# IMx6Q.net
KiCad netlist of a schematic drawn in Altium Designer
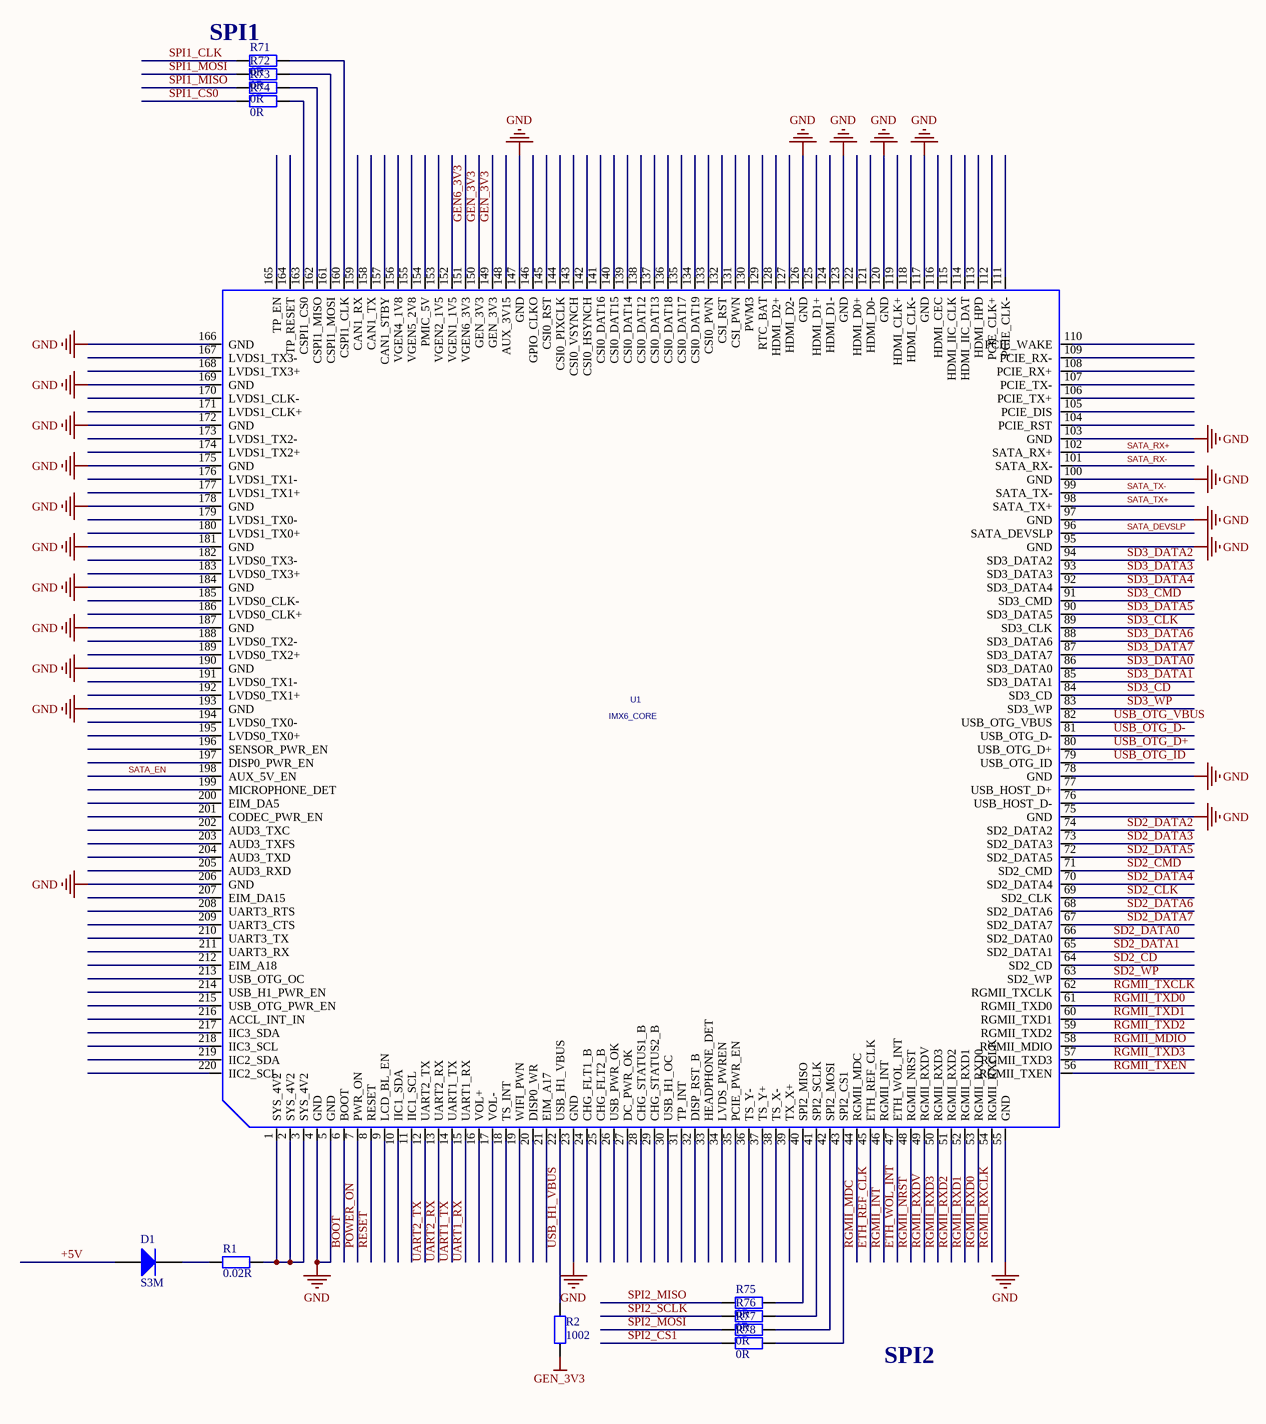
[diagram p0: IMx6Q.SchDoc]

(export (version "E")
  (design (tool "Eeschema 10.0.6"))
  (components
    (comp (ref "D1")
      (value "S3M")
      (footprint "DSO-C2/X3.3")
      (description "Default Diode")
      (fields (field (name "PUBLISHER") "Altium Limited"))
      (libsource (lib "Miscellaneous Devices") (part "Diode"))
    )
    (comp (ref "R1")
      (value "0.02R")
      (footprint "R1210")
      (description "Resistor")
      (fields (field (name "PUBLISHER") "Altium Limited"))
      (libsource (lib "") (part "Res2_1"))
    )
    (comp (ref "R2")
      (value "1002")
      (footprint "0603")
      (description "Resistor")
      (fields (field (name "PUBLISHER") "Altium Limited"))
      (libsource (lib "Miscellaneous Devices") (part "Res2"))
    )
    (comp (ref "R71") (value "0R") (footprint "0603") (libsource (lib "贴片电容电阻等") (part "电阻")))
    (comp (ref "R72") (value "0R") (footprint "0603") (libsource (lib "贴片电容电阻等") (part "电阻")))
    (comp (ref "R73") (value "0R") (footprint "0603") (libsource (lib "贴片电容电阻等") (part "电阻")))
    (comp (ref "R74") (value "0R") (footprint "0603") (libsource (lib "贴片电容电阻等") (part "电阻")))
    (comp (ref "R75") (value "0R") (footprint "0603") (libsource (lib "贴片电容电阻等") (part "电阻")))
    (comp (ref "R76") (value "0R") (footprint "0603") (libsource (lib "贴片电容电阻等") (part "电阻")))
    (comp (ref "R77") (value "0R") (footprint "0603") (libsource (lib "贴片电容电阻等") (part "电阻")))
    (comp (ref "R78") (value "0R") (footprint "0603") (libsource (lib "贴片电容电阻等") (part "电阻")))
    (comp (ref "U1") (value "IMX6_CORE") (footprint "IMX6_CORE") (libsource (lib "*") (part "IMX6_CORE")))
  )
  (nets
    (net (code "1") (name "/+5V") (class "Default")
      (node (ref "D1") (pin "1") (pinfunction "A_1") (pintype "passive"))
    )
    (net (code "2") (name "/BOOT") (class "Default")
      (node (ref "U1") (pin "6") (pinfunction "BOOT_6") (pintype "passive"))
    )
    (net (code "3") (name "/ETH_REF_CLK") (class "Default")
      (node (ref "U1") (pin "45") (pinfunction "ETH_REF_CLK_45") (pintype "passive"))
    )
    (net (code "4") (name "/ETH_WOL_INT") (class "Default")
      (node (ref "U1") (pin "47") (pinfunction "ETH_WOL_INT_47") (pintype "passive"))
    )
    (net (code "5") (name "/GEN6_3V3") (class "Default")
      (node (ref "U1") (pin "151") (pinfunction "VGEN6_3V3_151") (pintype "passive"))
    )
    (net (code "6") (name "/POWER_ON") (class "Default")
      (node (ref "U1") (pin "7") (pinfunction "PWR_ON_7") (pintype "passive"))
    )
    (net (code "7") (name "/RESET") (class "Default")
      (node (ref "U1") (pin "8") (pinfunction "RESET_8") (pintype "passive"))
    )
    (net (code "8") (name "/RGMII_INT") (class "Default")
      (node (ref "U1") (pin "46") (pinfunction "RGMII_INT_46") (pintype "passive"))
    )
    (net (code "9") (name "/RGMII_MDC") (class "Default")
      (node (ref "U1") (pin "44") (pinfunction "RGMII_MDC_44") (pintype "passive"))
    )
    (net (code "10") (name "/RGMII_MDIO") (class "Default")
      (node (ref "U1") (pin "58") (pinfunction "RGMII_MDIO_58") (pintype "passive"))
    )
    (net (code "11") (name "/RGMII_NRST") (class "Default")
      (node (ref "U1") (pin "48") (pinfunction "RGMII_NRST_48") (pintype "passive"))
    )
    (net (code "12") (name "/RGMII_RXCLK") (class "Default")
      (node (ref "U1") (pin "54") (pinfunction "RGMII_RXCLK_54") (pintype "passive"))
    )
    (net (code "13") (name "/RGMII_RXD0") (class "Default")
      (node (ref "U1") (pin "53") (pinfunction "RGMII_RXD0_53") (pintype "passive"))
    )
    (net (code "14") (name "/RGMII_RXD1") (class "Default")
      (node (ref "U1") (pin "52") (pinfunction "RGMII_RXD1_52") (pintype "passive"))
    )
    (net (code "15") (name "/RGMII_RXD2") (class "Default")
      (node (ref "U1") (pin "51") (pinfunction "RGMII_RXD2_51") (pintype "passive"))
    )
    (net (code "16") (name "/RGMII_RXD3") (class "Default")
      (node (ref "U1") (pin "50") (pinfunction "RGMII_RXD3_50") (pintype "passive"))
    )
    (net (code "17") (name "/RGMII_RXDV") (class "Default")
      (node (ref "U1") (pin "49") (pinfunction "RGMII_RXDV_49") (pintype "passive"))
    )
    (net (code "18") (name "/RGMII_TXCLK") (class "Default")
      (node (ref "U1") (pin "62") (pinfunction "RGMII_TXCLK_62") (pintype "passive"))
    )
    (net (code "19") (name "/RGMII_TXD0") (class "Default")
      (node (ref "U1") (pin "61") (pinfunction "RGMII_TXD0_61") (pintype "passive"))
    )
    (net (code "20") (name "/RGMII_TXD1") (class "Default")
      (node (ref "U1") (pin "60") (pinfunction "RGMII_TXD1_60") (pintype "passive"))
    )
    (net (code "21") (name "/RGMII_TXD2") (class "Default")
      (node (ref "U1") (pin "59") (pinfunction "RGMII_TXD2_59") (pintype "passive"))
    )
    (net (code "22") (name "/RGMII_TXD3") (class "Default")
      (node (ref "U1") (pin "57") (pinfunction "RGMII_TXD3_57") (pintype "passive"))
    )
    (net (code "23") (name "/RGMII_TXEN") (class "Default")
      (node (ref "U1") (pin "56") (pinfunction "RGMII_TXEN_56") (pintype "passive"))
    )
    (net (code "24") (name "/SATA_DEVSLP") (class "Default")
      (node (ref "U1") (pin "96") (pinfunction "SATA_DEVSLP_96") (pintype "passive"))
    )
    (net (code "25") (name "/SATA_EN") (class "Default")
      (node (ref "U1") (pin "198") (pinfunction "AUX_5V_EN_198") (pintype "passive"))
    )
    (net (code "26") (name "/SATA_RX+") (class "Default")
      (node (ref "U1") (pin "102") (pinfunction "SATA_RX+_102") (pintype "passive"))
    )
    (net (code "27") (name "/SATA_RX-") (class "Default")
      (node (ref "U1") (pin "101") (pinfunction "SATA_RX-_101") (pintype "passive"))
    )
    (net (code "28") (name "/SATA_TX+") (class "Default")
      (node (ref "U1") (pin "98") (pinfunction "SATA_TX+_98") (pintype "passive"))
    )
    (net (code "29") (name "/SATA_TX-") (class "Default")
      (node (ref "U1") (pin "99") (pinfunction "SATA_TX-_99") (pintype "passive"))
    )
    (net (code "30") (name "/SD2_CD") (class "Default")
      (node (ref "U1") (pin "64") (pinfunction "SD2_CD_64") (pintype "passive"))
    )
    (net (code "31") (name "/SD2_CLK") (class "Default")
      (node (ref "U1") (pin "69") (pinfunction "SD2_CLK_69") (pintype "passive"))
    )
    (net (code "32") (name "/SD2_CMD") (class "Default")
      (node (ref "U1") (pin "71") (pinfunction "SD2_CMD_71") (pintype "passive"))
    )
    (net (code "33") (name "/SD2_DATA0") (class "Default")
      (node (ref "U1") (pin "66") (pinfunction "SD2_DATA0_66") (pintype "passive"))
    )
    (net (code "34") (name "/SD2_DATA1") (class "Default")
      (node (ref "U1") (pin "65") (pinfunction "SD2_DATA1_65") (pintype "passive"))
    )
    (net (code "35") (name "/SD2_DATA2") (class "Default")
      (node (ref "U1") (pin "74") (pinfunction "SD2_DATA2_74") (pintype "passive"))
    )
    (net (code "36") (name "/SD2_DATA3") (class "Default")
      (node (ref "U1") (pin "73") (pinfunction "SD2_DATA3_73") (pintype "passive"))
    )
    (net (code "37") (name "/SD2_DATA4") (class "Default")
      (node (ref "U1") (pin "70") (pinfunction "SD2_DATA4_70") (pintype "passive"))
    )
    (net (code "38") (name "/SD2_DATA5") (class "Default")
      (node (ref "U1") (pin "72") (pinfunction "SD2_DATA5_72") (pintype "passive"))
    )
    (net (code "39") (name "/SD2_DATA6") (class "Default")
      (node (ref "U1") (pin "68") (pinfunction "SD2_DATA6_68") (pintype "passive"))
    )
    (net (code "40") (name "/SD2_DATA7") (class "Default")
      (node (ref "U1") (pin "67") (pinfunction "SD2_DATA7_67") (pintype "passive"))
    )
    (net (code "41") (name "/SD2_WP") (class "Default")
      (node (ref "U1") (pin "63") (pinfunction "SD2_WP_63") (pintype "passive"))
    )
    (net (code "42") (name "/SD3_CD") (class "Default")
      (node (ref "U1") (pin "84") (pinfunction "SD3_CD_84") (pintype "passive"))
    )
    (net (code "43") (name "/SD3_CLK") (class "Default")
      (node (ref "U1") (pin "89") (pinfunction "SD3_CLK_89") (pintype "passive"))
    )
    (net (code "44") (name "/SD3_CMD") (class "Default")
      (node (ref "U1") (pin "91") (pinfunction "SD3_CMD_91") (pintype "passive"))
    )
    (net (code "45") (name "/SD3_DATA0") (class "Default")
      (node (ref "U1") (pin "86") (pinfunction "SD3_DATA0_86") (pintype "passive"))
    )
    (net (code "46") (name "/SD3_DATA1") (class "Default")
      (node (ref "U1") (pin "85") (pinfunction "SD3_DATA1_85") (pintype "passive"))
    )
    (net (code "47") (name "/SD3_DATA2") (class "Default")
      (node (ref "U1") (pin "94") (pinfunction "SD3_DATA2_94") (pintype "passive"))
    )
    (net (code "48") (name "/SD3_DATA3") (class "Default")
      (node (ref "U1") (pin "93") (pinfunction "SD3_DATA3_93") (pintype "passive"))
    )
    (net (code "49") (name "/SD3_DATA4") (class "Default")
      (node (ref "U1") (pin "92") (pinfunction "SD3_DATA4_92") (pintype "passive"))
    )
    (net (code "50") (name "/SD3_DATA5") (class "Default")
      (node (ref "U1") (pin "90") (pinfunction "SD3_DATA5_90") (pintype "passive"))
    )
    (net (code "51") (name "/SD3_DATA6") (class "Default")
      (node (ref "U1") (pin "88") (pinfunction "SD3_DATA6_88") (pintype "passive"))
    )
    (net (code "52") (name "/SD3_DATA7") (class "Default")
      (node (ref "U1") (pin "87") (pinfunction "SD3_DATA7_87") (pintype "passive"))
    )
    (net (code "53") (name "/SD3_WP") (class "Default")
      (node (ref "U1") (pin "83") (pinfunction "SD3_WP_83") (pintype "passive"))
    )
    (net (code "54") (name "/SPI1_CLK") (class "Default")
      (node (ref "R71") (pin "2") (pinfunction "2_2") (pintype "passive"))
    )
    (net (code "55") (name "/SPI1_CS0") (class "Default")
      (node (ref "R74") (pin "2") (pinfunction "2_2") (pintype "passive"))
    )
    (net (code "56") (name "/SPI1_MISO") (class "Default")
      (node (ref "R73") (pin "2") (pinfunction "2_2") (pintype "passive"))
    )
    (net (code "57") (name "/SPI1_MOSI") (class "Default")
      (node (ref "R72") (pin "2") (pinfunction "2_2") (pintype "passive"))
    )
    (net (code "58") (name "/SPI2_CS1") (class "Default")
      (node (ref "R78") (pin "2") (pinfunction "2_2") (pintype "passive"))
    )
    (net (code "59") (name "/SPI2_MISO") (class "Default")
      (node (ref "R75") (pin "2") (pinfunction "2_2") (pintype "passive"))
    )
    (net (code "60") (name "/SPI2_MOSI") (class "Default")
      (node (ref "R77") (pin "2") (pinfunction "2_2") (pintype "passive"))
    )
    (net (code "61") (name "/SPI2_SCLK") (class "Default")
      (node (ref "R76") (pin "2") (pinfunction "2_2") (pintype "passive"))
    )
    (net (code "62") (name "/UART1_RX") (class "Default")
      (node (ref "U1") (pin "15") (pinfunction "UART1_RX_15") (pintype "passive"))
    )
    (net (code "63") (name "/UART1_TX") (class "Default")
      (node (ref "U1") (pin "14") (pinfunction "UART1_TX_14") (pintype "passive"))
    )
    (net (code "64") (name "/UART2_RX") (class "Default")
      (node (ref "U1") (pin "13") (pinfunction "UART2_RX_13") (pintype "passive"))
    )
    (net (code "65") (name "/UART2_TX") (class "Default")
      (node (ref "U1") (pin "12") (pinfunction "UART2_TX_12") (pintype "passive"))
    )
    (net (code "66") (name "/USB_H1_VBUS") (class "Default")
      (node (ref "R2") (pin "1") (pinfunction "1_1") (pintype "passive"))
      (node (ref "U1") (pin "22") (pinfunction "USB_H1_VBUS_22") (pintype "passive"))
    )
    (net (code "67") (name "/USB_OTG_D+") (class "Default")
      (node (ref "U1") (pin "80") (pinfunction "USB_OTG_D+_80") (pintype "passive"))
    )
    (net (code "68") (name "/USB_OTG_D-") (class "Default")
      (node (ref "U1") (pin "81") (pinfunction "USB_OTG_D-_81") (pintype "passive"))
    )
    (net (code "69") (name "/USB_OTG_ID") (class "Default")
      (node (ref "U1") (pin "79") (pinfunction "USB_OTG_ID_79") (pintype "passive"))
    )
    (net (code "70") (name "/USB_OTG_VBUS") (class "Default")
      (node (ref "U1") (pin "82") (pinfunction "USB_OTG_VBUS_82") (pintype "passive"))
    )
    (net (code "71") (name "GEN_3V3") (class "Default")
      (node (ref "R2") (pin "2") (pinfunction "2_2") (pintype "passive"))
      (node (ref "U1") (pin "149") (pinfunction "GEN_3V3_149") (pintype "passive"))
      (node (ref "U1") (pin "150") (pinfunction "GEN_3V3_150") (pintype "passive"))
    )
    (net (code "72") (name "GND") (class "Default")
      (node (ref "U1") (pin "100") (pinfunction "GND_100") (pintype "passive"))
      (node (ref "U1") (pin "103") (pinfunction "GND_103") (pintype "passive"))
      (node (ref "U1") (pin "117") (pinfunction "GND_117") (pintype "passive"))
      (node (ref "U1") (pin "120") (pinfunction "GND_120") (pintype "passive"))
      (node (ref "U1") (pin "123") (pinfunction "GND_123") (pintype "passive"))
      (node (ref "U1") (pin "126") (pinfunction "GND_126") (pintype "passive"))
      (node (ref "U1") (pin "147") (pinfunction "GND_147") (pintype "passive"))
      (node (ref "U1") (pin "166") (pinfunction "GND_166") (pintype "passive"))
      (node (ref "U1") (pin "169") (pinfunction "GND_169") (pintype "passive"))
      (node (ref "U1") (pin "172") (pinfunction "GND_172") (pintype "passive"))
      (node (ref "U1") (pin "175") (pinfunction "GND_175") (pintype "passive"))
      (node (ref "U1") (pin "178") (pinfunction "GND_178") (pintype "passive"))
      (node (ref "U1") (pin "181") (pinfunction "GND_181") (pintype "passive"))
      (node (ref "U1") (pin "184") (pinfunction "GND_184") (pintype "passive"))
      (node (ref "U1") (pin "187") (pinfunction "GND_187") (pintype "passive"))
      (node (ref "U1") (pin "190") (pinfunction "GND_190") (pintype "passive"))
      (node (ref "U1") (pin "193") (pinfunction "GND_193") (pintype "passive"))
      (node (ref "U1") (pin "206") (pinfunction "GND_206") (pintype "passive"))
      (node (ref "U1") (pin "23") (pinfunction "GND_23") (pintype "passive"))
      (node (ref "U1") (pin "4") (pinfunction "GND_4") (pintype "passive"))
      (node (ref "U1") (pin "5") (pinfunction "GND_5") (pintype "passive"))
      (node (ref "U1") (pin "55") (pinfunction "GND_55") (pintype "passive"))
      (node (ref "U1") (pin "75") (pinfunction "GND_75") (pintype "passive"))
      (node (ref "U1") (pin "78") (pinfunction "GND_78") (pintype "passive"))
      (node (ref "U1") (pin "95") (pinfunction "GND_95") (pintype "passive"))
      (node (ref "U1") (pin "97") (pinfunction "GND_97") (pintype "passive"))
    )
    (net (code "73") (name "Net-(D1-K)") (class "Default")
      (node (ref "D1") (pin "2") (pinfunction "K_2") (pintype "passive"))
      (node (ref "R1") (pin "1") (pinfunction "1_1") (pintype "passive"))
    )
    (net (code "74") (name "Net-(R1-Pad2)") (class "Default")
      (node (ref "R1") (pin "2") (pinfunction "2_2") (pintype "passive"))
      (node (ref "U1") (pin "1") (pinfunction "SYS_4V2_1") (pintype "passive"))
      (node (ref "U1") (pin "2") (pinfunction "SYS_4V2_2") (pintype "passive"))
      (node (ref "U1") (pin "3") (pinfunction "SYS_4V2_3") (pintype "passive"))
    )
    (net (code "75") (name "Net-(U1-CSPI1_CLK)") (class "Default")
      (node (ref "R71") (pin "1") (pinfunction "1_1") (pintype "passive"))
      (node (ref "U1") (pin "160") (pinfunction "CSPI1_CLK_160") (pintype "passive"))
    )
    (net (code "76") (name "Net-(U1-CSPI1_CS0)") (class "Default")
      (node (ref "R74") (pin "1") (pinfunction "1_1") (pintype "passive"))
      (node (ref "U1") (pin "163") (pinfunction "CSPI1_CS0_163") (pintype "passive"))
    )
    (net (code "77") (name "Net-(U1-CSPI1_MISO)") (class "Default")
      (node (ref "R73") (pin "1") (pinfunction "1_1") (pintype "passive"))
      (node (ref "U1") (pin "162") (pinfunction "CSPI1_MISO_162") (pintype "passive"))
    )
    (net (code "78") (name "Net-(U1-CSPI1_MOSI)") (class "Default")
      (node (ref "R72") (pin "1") (pinfunction "1_1") (pintype "passive"))
      (node (ref "U1") (pin "161") (pinfunction "CSPI1_MOSI_161") (pintype "passive"))
    )
    (net (code "79") (name "Net-(U1-SPI2_CS1)") (class "Default")
      (node (ref "R78") (pin "1") (pinfunction "1_1") (pintype "passive"))
      (node (ref "U1") (pin "43") (pinfunction "SPI2_CS1_43") (pintype "passive"))
    )
    (net (code "80") (name "Net-(U1-SPI2_MISO)") (class "Default")
      (node (ref "R75") (pin "1") (pinfunction "1_1") (pintype "passive"))
      (node (ref "U1") (pin "40") (pinfunction "SPI2_MISO_40") (pintype "passive"))
    )
    (net (code "81") (name "Net-(U1-SPI2_MOSI)") (class "Default")
      (node (ref "R77") (pin "1") (pinfunction "1_1") (pintype "passive"))
      (node (ref "U1") (pin "42") (pinfunction "SPI2_MOSI_42") (pintype "passive"))
    )
    (net (code "82") (name "Net-(U1-SPI2_SCLK)") (class "Default")
      (node (ref "R76") (pin "1") (pinfunction "1_1") (pintype "passive"))
      (node (ref "U1") (pin "41") (pinfunction "SPI2_SCLK_41") (pintype "passive"))
    )
    (net (code "83") (name "unconnected-(U1-ACCL_INT_IN-Pad216)") (class "Default")
      (node (ref "U1") (pin "216") (pinfunction "ACCL_INT_IN_216") (pintype "passive"))
    )
    (net (code "84") (name "unconnected-(U1-AUD3_RXD-Pad205)") (class "Default")
      (node (ref "U1") (pin "205") (pinfunction "AUD3_RXD_205") (pintype "passive"))
    )
    (net (code "85") (name "unconnected-(U1-AUD3_TXC-Pad202)") (class "Default")
      (node (ref "U1") (pin "202") (pinfunction "AUD3_TXC_202") (pintype "passive"))
    )
    (net (code "86") (name "unconnected-(U1-AUD3_TXD-Pad204)") (class "Default")
      (node (ref "U1") (pin "204") (pinfunction "AUD3_TXD_204") (pintype "passive"))
    )
    (net (code "87") (name "unconnected-(U1-AUD3_TXFS-Pad203)") (class "Default")
      (node (ref "U1") (pin "203") (pinfunction "AUD3_TXFS_203") (pintype "passive"))
    )
    (net (code "88") (name "unconnected-(U1-AUX_3V15-Pad148)") (class "Default")
      (node (ref "U1") (pin "148") (pinfunction "AUX_3V15_148") (pintype "passive"))
    )
    (net (code "89") (name "unconnected-(U1-CAN1_RX-Pad159)") (class "Default")
      (node (ref "U1") (pin "159") (pinfunction "CAN1_RX_159") (pintype "passive"))
    )
    (net (code "90") (name "unconnected-(U1-CAN1_STBY-Pad157)") (class "Default")
      (node (ref "U1") (pin "157") (pinfunction "CAN1_STBY_157") (pintype "passive"))
    )
    (net (code "91") (name "unconnected-(U1-CAN1_TX-Pad158)") (class "Default")
      (node (ref "U1") (pin "158") (pinfunction "CAN1_TX_158") (pintype "passive"))
    )
    (net (code "92") (name "unconnected-(U1-CHG_FLT1_B-Pad24)") (class "Default")
      (node (ref "U1") (pin "24") (pinfunction "CHG_FLT1_B_24") (pintype "passive"))
    )
    (net (code "93") (name "unconnected-(U1-CHG_FLT2_B-Pad25)") (class "Default")
      (node (ref "U1") (pin "25") (pinfunction "CHG_FLT2_B_25") (pintype "passive"))
    )
    (net (code "94") (name "unconnected-(U1-CHG_STATUS1_B-Pad28)") (class "Default")
      (node (ref "U1") (pin "28") (pinfunction "CHG_STATUS1_B_28") (pintype "passive"))
    )
    (net (code "95") (name "unconnected-(U1-CHG_STATUS2_B-Pad29)") (class "Default")
      (node (ref "U1") (pin "29") (pinfunction "CHG_STATUS2_B_29") (pintype "passive"))
    )
    (net (code "96") (name "unconnected-(U1-CODEC_PWR_EN-Pad201)") (class "Default")
      (node (ref "U1") (pin "201") (pinfunction "CODEC_PWR_EN_201") (pintype "passive"))
    )
    (net (code "97") (name "unconnected-(U1-CSI0_DAT12-Pad138)") (class "Default")
      (node (ref "U1") (pin "138") (pinfunction "CSI0_DAT12_138") (pintype "passive"))
    )
    (net (code "98") (name "unconnected-(U1-CSI0_DAT13-Pad137)") (class "Default")
      (node (ref "U1") (pin "137") (pinfunction "CSI0_DAT13_137") (pintype "passive"))
    )
    (net (code "99") (name "unconnected-(U1-CSI0_DAT14-Pad139)") (class "Default")
      (node (ref "U1") (pin "139") (pinfunction "CSI0_DAT14_139") (pintype "passive"))
    )
    (net (code "100") (name "unconnected-(U1-CSI0_DAT15-Pad140)") (class "Default")
      (node (ref "U1") (pin "140") (pinfunction "CSI0_DAT15_140") (pintype "passive"))
    )
    (net (code "101") (name "unconnected-(U1-CSI0_DAT16-Pad141)") (class "Default")
      (node (ref "U1") (pin "141") (pinfunction "CSI0_DAT16_141") (pintype "passive"))
    )
    (net (code "102") (name "unconnected-(U1-CSI0_DAT17-Pad135)") (class "Default")
      (node (ref "U1") (pin "135") (pinfunction "CSI0_DAT17_135") (pintype "passive"))
    )
    (net (code "103") (name "unconnected-(U1-CSI0_DAT18-Pad136)") (class "Default")
      (node (ref "U1") (pin "136") (pinfunction "CSI0_DAT18_136") (pintype "passive"))
    )
    (net (code "104") (name "unconnected-(U1-CSI0_DAT19-Pad134)") (class "Default")
      (node (ref "U1") (pin "134") (pinfunction "CSI0_DAT19_134") (pintype "passive"))
    )
    (net (code "105") (name "unconnected-(U1-CSI0_HSYNCH-Pad142)") (class "Default")
      (node (ref "U1") (pin "142") (pinfunction "CSI0_HSYNCH_142") (pintype "passive"))
    )
    (net (code "106") (name "unconnected-(U1-CSI0_PIXCLK-Pad144)") (class "Default")
      (node (ref "U1") (pin "144") (pinfunction "CSI0_PIXCLK_144") (pintype "passive"))
    )
    (net (code "107") (name "unconnected-(U1-CSI0_PWN-Pad133)") (class "Default")
      (node (ref "U1") (pin "133") (pinfunction "CSI0_PWN_133") (pintype "passive"))
    )
    (net (code "108") (name "unconnected-(U1-CSI0_RST-Pad145)") (class "Default")
      (node (ref "U1") (pin "145") (pinfunction "CSI0_RST_145") (pintype "passive"))
    )
    (net (code "109") (name "unconnected-(U1-CSI0_VSYNCH-Pad143)") (class "Default")
      (node (ref "U1") (pin "143") (pinfunction "CSI0_VSYNCH_143") (pintype "passive"))
    )
    (net (code "110") (name "unconnected-(U1-CSI_PWN-Pad131)") (class "Default")
      (node (ref "U1") (pin "131") (pinfunction "CSI_PWN_131") (pintype "passive"))
    )
    (net (code "111") (name "unconnected-(U1-CSI_RST-Pad132)") (class "Default")
      (node (ref "U1") (pin "132") (pinfunction "CSI_RST_132") (pintype "passive"))
    )
    (net (code "112") (name "unconnected-(U1-DC_PWR_OK-Pad27)") (class "Default")
      (node (ref "U1") (pin "27") (pinfunction "DC_PWR_OK_27") (pintype "passive"))
    )
    (net (code "113") (name "unconnected-(U1-DISP0_PWR_EN-Pad197)") (class "Default")
      (node (ref "U1") (pin "197") (pinfunction "DISP0_PWR_EN_197") (pintype "passive"))
    )
    (net (code "114") (name "unconnected-(U1-DISP0_WR-Pad20)") (class "Default")
      (node (ref "U1") (pin "20") (pinfunction "DISP0_WR_20") (pintype "passive"))
    )
    (net (code "115") (name "unconnected-(U1-DISP_RST_B-Pad32)") (class "Default")
      (node (ref "U1") (pin "32") (pinfunction "DISP_RST_B_32") (pintype "passive"))
    )
    (net (code "116") (name "unconnected-(U1-EIM_A17-Pad21)") (class "Default")
      (node (ref "U1") (pin "21") (pinfunction "EIM_A17_21") (pintype "passive"))
    )
    (net (code "117") (name "unconnected-(U1-EIM_A18-Pad212)") (class "Default")
      (node (ref "U1") (pin "212") (pinfunction "EIM_A18_212") (pintype "passive"))
    )
    (net (code "118") (name "unconnected-(U1-EIM_DA5-Pad200)") (class "Default")
      (node (ref "U1") (pin "200") (pinfunction "EIM_DA5_200") (pintype "passive"))
    )
    (net (code "119") (name "unconnected-(U1-EIM_DA15-Pad207)") (class "Default")
      (node (ref "U1") (pin "207") (pinfunction "EIM_DA15_207") (pintype "passive"))
    )
    (net (code "120") (name "unconnected-(U1-GPIO_CLKO-Pad146)") (class "Default")
      (node (ref "U1") (pin "146") (pinfunction "GPIO_CLKO_146") (pintype "passive"))
    )
    (net (code "121") (name "unconnected-(U1-HDMI_CEC-Pad116)") (class "Default")
      (node (ref "U1") (pin "116") (pinfunction "HDMI_CEC_116") (pintype "passive"))
    )
    (net (code "122") (name "unconnected-(U1-HDMI_CLK+-Pad119)") (class "Default")
      (node (ref "U1") (pin "119") (pinfunction "HDMI_CLK+_119") (pintype "passive"))
    )
    (net (code "123") (name "unconnected-(U1-HDMI_CLK--Pad118)") (class "Default")
      (node (ref "U1") (pin "118") (pinfunction "HDMI_CLK-_118") (pintype "passive"))
    )
    (net (code "124") (name "unconnected-(U1-HDMI_D0+-Pad122)") (class "Default")
      (node (ref "U1") (pin "122") (pinfunction "HDMI_D0+_122") (pintype "passive"))
    )
    (net (code "125") (name "unconnected-(U1-HDMI_D0--Pad121)") (class "Default")
      (node (ref "U1") (pin "121") (pinfunction "HDMI_D0-_121") (pintype "passive"))
    )
    (net (code "126") (name "unconnected-(U1-HDMI_D1+-Pad125)") (class "Default")
      (node (ref "U1") (pin "125") (pinfunction "HDMI_D1+_125") (pintype "passive"))
    )
    (net (code "127") (name "unconnected-(U1-HDMI_D1--Pad124)") (class "Default")
      (node (ref "U1") (pin "124") (pinfunction "HDMI_D1-_124") (pintype "passive"))
    )
    (net (code "128") (name "unconnected-(U1-HDMI_D2+-Pad128)") (class "Default")
      (node (ref "U1") (pin "128") (pinfunction "HDMI_D2+_128") (pintype "passive"))
    )
    (net (code "129") (name "unconnected-(U1-HDMI_D2--Pad127)") (class "Default")
      (node (ref "U1") (pin "127") (pinfunction "HDMI_D2-_127") (pintype "passive"))
    )
    (net (code "130") (name "unconnected-(U1-HDMI_HPD-Pad113)") (class "Default")
      (node (ref "U1") (pin "113") (pinfunction "HDMI_HPD_113") (pintype "passive"))
    )
    (net (code "131") (name "unconnected-(U1-HDMI_IIC_CLK-Pad115)") (class "Default")
      (node (ref "U1") (pin "115") (pinfunction "HDMI_IIC_CLK_115") (pintype "passive"))
    )
    (net (code "132") (name "unconnected-(U1-HDMI_IIC_DAT-Pad114)") (class "Default")
      (node (ref "U1") (pin "114") (pinfunction "HDMI_IIC_DAT_114") (pintype "passive"))
    )
    (net (code "133") (name "unconnected-(U1-HEADPHONE_DET-Pad33)") (class "Default")
      (node (ref "U1") (pin "33") (pinfunction "HEADPHONE_DET_33") (pintype "passive"))
    )
    (net (code "134") (name "unconnected-(U1-IIC1_SCL-Pad11)") (class "Default")
      (node (ref "U1") (pin "11") (pinfunction "IIC1_SCL_11") (pintype "passive"))
    )
    (net (code "135") (name "unconnected-(U1-IIC1_SDA-Pad10)") (class "Default")
      (node (ref "U1") (pin "10") (pinfunction "IIC1_SDA_10") (pintype "passive"))
    )
    (net (code "136") (name "unconnected-(U1-IIC2_SCL-Pad220)") (class "Default")
      (node (ref "U1") (pin "220") (pinfunction "IIC2_SCL_220") (pintype "passive"))
    )
    (net (code "137") (name "unconnected-(U1-IIC2_SDA-Pad219)") (class "Default")
      (node (ref "U1") (pin "219") (pinfunction "IIC2_SDA_219") (pintype "passive"))
    )
    (net (code "138") (name "unconnected-(U1-IIC3_SCL-Pad218)") (class "Default")
      (node (ref "U1") (pin "218") (pinfunction "IIC3_SCL_218") (pintype "passive"))
    )
    (net (code "139") (name "unconnected-(U1-IIC3_SDA-Pad217)") (class "Default")
      (node (ref "U1") (pin "217") (pinfunction "IIC3_SDA_217") (pintype "passive"))
    )
    (net (code "140") (name "unconnected-(U1-LCD_BL_EN-Pad9)") (class "Default")
      (node (ref "U1") (pin "9") (pinfunction "LCD_BL_EN_9") (pintype "passive"))
    )
    (net (code "141") (name "unconnected-(U1-LVDS0_CLK+-Pad186)") (class "Default")
      (node (ref "U1") (pin "186") (pinfunction "LVDS0_CLK+_186") (pintype "passive"))
    )
    (net (code "142") (name "unconnected-(U1-LVDS0_CLK--Pad185)") (class "Default")
      (node (ref "U1") (pin "185") (pinfunction "LVDS0_CLK-_185") (pintype "passive"))
    )
    (net (code "143") (name "unconnected-(U1-LVDS0_TX0+-Pad195)") (class "Default")
      (node (ref "U1") (pin "195") (pinfunction "LVDS0_TX0+_195") (pintype "passive"))
    )
    (net (code "144") (name "unconnected-(U1-LVDS0_TX0--Pad194)") (class "Default")
      (node (ref "U1") (pin "194") (pinfunction "LVDS0_TX0-_194") (pintype "passive"))
    )
    (net (code "145") (name "unconnected-(U1-LVDS0_TX1+-Pad192)") (class "Default")
      (node (ref "U1") (pin "192") (pinfunction "LVDS0_TX1+_192") (pintype "passive"))
    )
    (net (code "146") (name "unconnected-(U1-LVDS0_TX1--Pad191)") (class "Default")
      (node (ref "U1") (pin "191") (pinfunction "LVDS0_TX1-_191") (pintype "passive"))
    )
    (net (code "147") (name "unconnected-(U1-LVDS0_TX2+-Pad189)") (class "Default")
      (node (ref "U1") (pin "189") (pinfunction "LVDS0_TX2+_189") (pintype "passive"))
    )
    (net (code "148") (name "unconnected-(U1-LVDS0_TX2--Pad188)") (class "Default")
      (node (ref "U1") (pin "188") (pinfunction "LVDS0_TX2-_188") (pintype "passive"))
    )
    (net (code "149") (name "unconnected-(U1-LVDS0_TX3+-Pad183)") (class "Default")
      (node (ref "U1") (pin "183") (pinfunction "LVDS0_TX3+_183") (pintype "passive"))
    )
    (net (code "150") (name "unconnected-(U1-LVDS0_TX3--Pad182)") (class "Default")
      (node (ref "U1") (pin "182") (pinfunction "LVDS0_TX3-_182") (pintype "passive"))
    )
    (net (code "151") (name "unconnected-(U1-LVDS1_CLK+-Pad171)") (class "Default")
      (node (ref "U1") (pin "171") (pinfunction "LVDS1_CLK+_171") (pintype "passive"))
    )
    (net (code "152") (name "unconnected-(U1-LVDS1_CLK--Pad170)") (class "Default")
      (node (ref "U1") (pin "170") (pinfunction "LVDS1_CLK-_170") (pintype "passive"))
    )
    (net (code "153") (name "unconnected-(U1-LVDS1_TX0+-Pad180)") (class "Default")
      (node (ref "U1") (pin "180") (pinfunction "LVDS1_TX0+_180") (pintype "passive"))
    )
    (net (code "154") (name "unconnected-(U1-LVDS1_TX0--Pad179)") (class "Default")
      (node (ref "U1") (pin "179") (pinfunction "LVDS1_TX0-_179") (pintype "passive"))
    )
    (net (code "155") (name "unconnected-(U1-LVDS1_TX1+-Pad177)") (class "Default")
      (node (ref "U1") (pin "177") (pinfunction "LVDS1_TX1+_177") (pintype "passive"))
    )
    (net (code "156") (name "unconnected-(U1-LVDS1_TX1--Pad176)") (class "Default")
      (node (ref "U1") (pin "176") (pinfunction "LVDS1_TX1-_176") (pintype "passive"))
    )
    (net (code "157") (name "unconnected-(U1-LVDS1_TX2+-Pad174)") (class "Default")
      (node (ref "U1") (pin "174") (pinfunction "LVDS1_TX2+_174") (pintype "passive"))
    )
    (net (code "158") (name "unconnected-(U1-LVDS1_TX2--Pad173)") (class "Default")
      (node (ref "U1") (pin "173") (pinfunction "LVDS1_TX2-_173") (pintype "passive"))
    )
    (net (code "159") (name "unconnected-(U1-LVDS1_TX3+-Pad168)") (class "Default")
      (node (ref "U1") (pin "168") (pinfunction "LVDS1_TX3+_168") (pintype "passive"))
    )
    (net (code "160") (name "unconnected-(U1-LVDS1_TX3--Pad167)") (class "Default")
      (node (ref "U1") (pin "167") (pinfunction "LVDS1_TX3-_167") (pintype "passive"))
    )
    (net (code "161") (name "unconnected-(U1-LVDS_PWREN-Pad34)") (class "Default")
      (node (ref "U1") (pin "34") (pinfunction "LVDS_PWREN_34") (pintype "passive"))
    )
    (net (code "162") (name "unconnected-(U1-MICROPHONE_DET-Pad199)") (class "Default")
      (node (ref "U1") (pin "199") (pinfunction "MICROPHONE_DET_199") (pintype "passive"))
    )
    (net (code "163") (name "unconnected-(U1-PCIE_CLK+-Pad112)") (class "Default")
      (node (ref "U1") (pin "112") (pinfunction "PCIE_CLK+_112") (pintype "passive"))
    )
    (net (code "164") (name "unconnected-(U1-PCIE_CLK--Pad111)") (class "Default")
      (node (ref "U1") (pin "111") (pinfunction "PCIE_CLK-_111") (pintype "passive"))
    )
    (net (code "165") (name "unconnected-(U1-PCIE_DIS-Pad105)") (class "Default")
      (node (ref "U1") (pin "105") (pinfunction "PCIE_DIS_105") (pintype "passive"))
    )
    (net (code "166") (name "unconnected-(U1-PCIE_PWR_EN-Pad35)") (class "Default")
      (node (ref "U1") (pin "35") (pinfunction "PCIE_PWR_EN_35") (pintype "passive"))
    )
    (net (code "167") (name "unconnected-(U1-PCIE_RST-Pad104)") (class "Default")
      (node (ref "U1") (pin "104") (pinfunction "PCIE_RST_104") (pintype "passive"))
    )
    (net (code "168") (name "unconnected-(U1-PCIE_RX+-Pad108)") (class "Default")
      (node (ref "U1") (pin "108") (pinfunction "PCIE_RX+_108") (pintype "passive"))
    )
    (net (code "169") (name "unconnected-(U1-PCIE_RX--Pad109)") (class "Default")
      (node (ref "U1") (pin "109") (pinfunction "PCIE_RX-_109") (pintype "passive"))
    )
    (net (code "170") (name "unconnected-(U1-PCIE_TX+-Pad106)") (class "Default")
      (node (ref "U1") (pin "106") (pinfunction "PCIE_TX+_106") (pintype "passive"))
    )
    (net (code "171") (name "unconnected-(U1-PCIE_TX--Pad107)") (class "Default")
      (node (ref "U1") (pin "107") (pinfunction "PCIE_TX-_107") (pintype "passive"))
    )
    (net (code "172") (name "unconnected-(U1-PCIE_WAKE-Pad110)") (class "Default")
      (node (ref "U1") (pin "110") (pinfunction "PCIE_WAKE_110") (pintype "passive"))
    )
    (net (code "173") (name "unconnected-(U1-PMIC_5V-Pad154)") (class "Default")
      (node (ref "U1") (pin "154") (pinfunction "PMIC_5V_154") (pintype "passive"))
    )
    (net (code "174") (name "unconnected-(U1-PWM3-Pad130)") (class "Default")
      (node (ref "U1") (pin "130") (pinfunction "PWM3_130") (pintype "passive"))
    )
    (net (code "175") (name "unconnected-(U1-RTC_BAT-Pad129)") (class "Default")
      (node (ref "U1") (pin "129") (pinfunction "RTC_BAT_129") (pintype "passive"))
    )
    (net (code "176") (name "unconnected-(U1-SENSOR_PWR_EN-Pad196)") (class "Default")
      (node (ref "U1") (pin "196") (pinfunction "SENSOR_PWR_EN_196") (pintype "passive"))
    )
    (net (code "177") (name "unconnected-(U1-TP_EN-Pad165)") (class "Default")
      (node (ref "U1") (pin "165") (pinfunction "TP_EN_165") (pintype "passive"))
    )
    (net (code "178") (name "unconnected-(U1-TP_INT-Pad31)") (class "Default")
      (node (ref "U1") (pin "31") (pinfunction "TP_INT_31") (pintype "passive"))
    )
    (net (code "179") (name "unconnected-(U1-TP_RESET-Pad164)") (class "Default")
      (node (ref "U1") (pin "164") (pinfunction "TP_RESET_164") (pintype "passive"))
    )
    (net (code "180") (name "unconnected-(U1-TS_INT-Pad18)") (class "Default")
      (node (ref "U1") (pin "18") (pinfunction "TS_INT_18") (pintype "passive"))
    )
    (net (code "181") (name "unconnected-(U1-TS_X--Pad38)") (class "Default")
      (node (ref "U1") (pin "38") (pinfunction "TS_X-_38") (pintype "passive"))
    )
    (net (code "182") (name "unconnected-(U1-TS_Y+-Pad37)") (class "Default")
      (node (ref "U1") (pin "37") (pinfunction "TS_Y+_37") (pintype "passive"))
    )
    (net (code "183") (name "unconnected-(U1-TS_Y--Pad36)") (class "Default")
      (node (ref "U1") (pin "36") (pinfunction "TS_Y-_36") (pintype "passive"))
    )
    (net (code "184") (name "unconnected-(U1-TX_X+-Pad39)") (class "Default")
      (node (ref "U1") (pin "39") (pinfunction "TX_X+_39") (pintype "passive"))
    )
    (net (code "185") (name "unconnected-(U1-UART3_CTS-Pad209)") (class "Default")
      (node (ref "U1") (pin "209") (pinfunction "UART3_CTS_209") (pintype "passive"))
    )
    (net (code "186") (name "unconnected-(U1-UART3_RTS-Pad208)") (class "Default")
      (node (ref "U1") (pin "208") (pinfunction "UART3_RTS_208") (pintype "passive"))
    )
    (net (code "187") (name "unconnected-(U1-UART3_RX-Pad211)") (class "Default")
      (node (ref "U1") (pin "211") (pinfunction "UART3_RX_211") (pintype "passive"))
    )
    (net (code "188") (name "unconnected-(U1-UART3_TX-Pad210)") (class "Default")
      (node (ref "U1") (pin "210") (pinfunction "UART3_TX_210") (pintype "passive"))
    )
    (net (code "189") (name "unconnected-(U1-USB_H1_OC-Pad30)") (class "Default")
      (node (ref "U1") (pin "30") (pinfunction "USB_H1_OC_30") (pintype "passive"))
    )
    (net (code "190") (name "unconnected-(U1-USB_H1_PWR_EN-Pad214)") (class "Default")
      (node (ref "U1") (pin "214") (pinfunction "USB_H1_PWR_EN_214") (pintype "passive"))
    )
    (net (code "191") (name "unconnected-(U1-USB_HOST_D+-Pad77)") (class "Default")
      (node (ref "U1") (pin "77") (pinfunction "USB_HOST_D+_77") (pintype "passive"))
    )
    (net (code "192") (name "unconnected-(U1-USB_HOST_D--Pad76)") (class "Default")
      (node (ref "U1") (pin "76") (pinfunction "USB_HOST_D-_76") (pintype "passive"))
    )
    (net (code "193") (name "unconnected-(U1-USB_OTG_OC-Pad213)") (class "Default")
      (node (ref "U1") (pin "213") (pinfunction "USB_OTG_OC_213") (pintype "passive"))
    )
    (net (code "194") (name "unconnected-(U1-USB_OTG_PWR_EN-Pad215)") (class "Default")
      (node (ref "U1") (pin "215") (pinfunction "USB_OTG_PWR_EN_215") (pintype "passive"))
    )
    (net (code "195") (name "unconnected-(U1-USB_PWR_OK-Pad26)") (class "Default")
      (node (ref "U1") (pin "26") (pinfunction "USB_PWR_OK_26") (pintype "passive"))
    )
    (net (code "196") (name "unconnected-(U1-VGEN1_1V5-Pad152)") (class "Default")
      (node (ref "U1") (pin "152") (pinfunction "VGEN1_1V5_152") (pintype "passive"))
    )
    (net (code "197") (name "unconnected-(U1-VGEN2_1V5-Pad153)") (class "Default")
      (node (ref "U1") (pin "153") (pinfunction "VGEN2_1V5_153") (pintype "passive"))
    )
    (net (code "198") (name "unconnected-(U1-VGEN4_1V8-Pad156)") (class "Default")
      (node (ref "U1") (pin "156") (pinfunction "VGEN4_1V8_156") (pintype "passive"))
    )
    (net (code "199") (name "unconnected-(U1-VGEN5_2V8-Pad155)") (class "Default")
      (node (ref "U1") (pin "155") (pinfunction "VGEN5_2V8_155") (pintype "passive"))
    )
    (net (code "200") (name "unconnected-(U1-VOL+-Pad16)") (class "Default")
      (node (ref "U1") (pin "16") (pinfunction "VOL+_16") (pintype "passive"))
    )
    (net (code "201") (name "unconnected-(U1-VOL--Pad17)") (class "Default")
      (node (ref "U1") (pin "17") (pinfunction "VOL-_17") (pintype "passive"))
    )
    (net (code "202") (name "unconnected-(U1-WIFI_PWN-Pad19)") (class "Default")
      (node (ref "U1") (pin "19") (pinfunction "WIFI_PWN_19") (pintype "passive"))
    )
  )
)
